# aiotsixsense.net
KiCad netlist of a schematic drawn in EAGLE
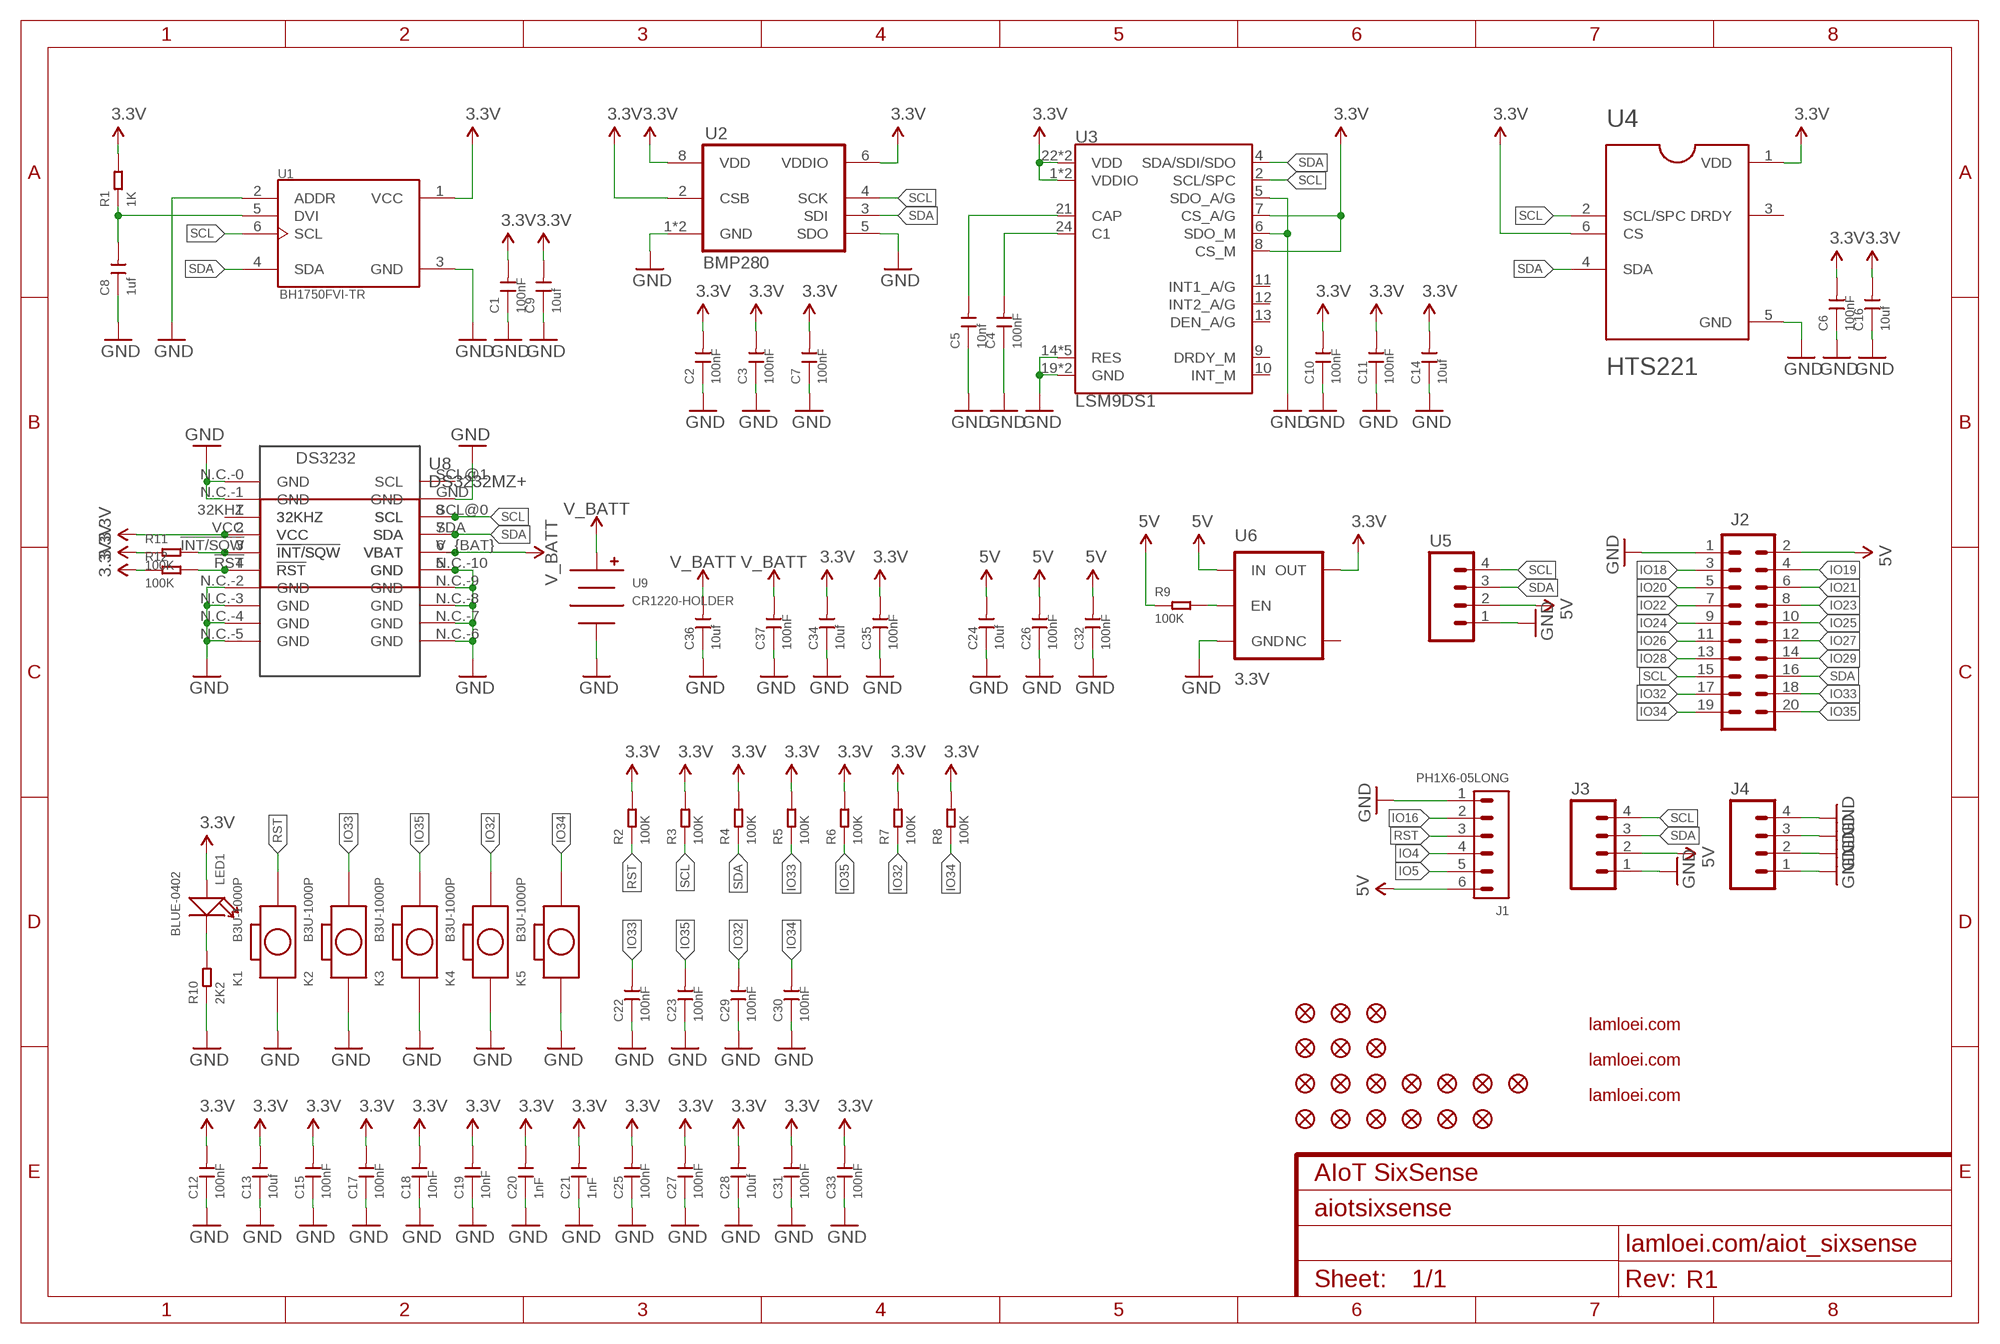
[diagram p0: schematic, sheet 1]

(export (version "E")
  (design (tool "Eeschema 10.0.6"))
  (components
    (comp (ref "C1")
      (value "100nF")
      (footprint "eagle-import:C0402")
      (fields (field (name "MPN") "CC0402JRNPO9BN470"))
      (libsource (lib "eagle-import") (part "CERAMIC-47PF-50V-5%-NP0(0402)"))
    )
    (comp (ref "C2")
      (value "100nF")
      (footprint "eagle-import:C0402")
      (fields (field (name "MPN") "CC0402JRNPO9BN470"))
      (libsource (lib "eagle-import") (part "CERAMIC-47PF-50V-5%-NP0(0402)"))
    )
    (comp (ref "C3")
      (value "100nF")
      (footprint "eagle-import:C0402")
      (fields (field (name "MPN") "CC0402JRNPO9BN470"))
      (libsource (lib "eagle-import") (part "CERAMIC-47PF-50V-5%-NP0(0402)"))
    )
    (comp (ref "C4")
      (value "100nF")
      (footprint "eagle-import:C0402")
      (fields (field (name "MPN") "CC0402JRNPO9BN470"))
      (libsource (lib "eagle-import") (part "CERAMIC-47PF-50V-5%-NP0(0402)"))
    )
    (comp (ref "C5")
      (value "10nf")
      (footprint "eagle-import:C0402")
      (fields (field (name "MPN") "CC0402KRX7R9BB103"))
      (libsource (lib "eagle-import") (part "CERAMIC-10NF-50V-10%-X7R(0402)"))
    )
    (comp (ref "C6")
      (value "100nF")
      (footprint "eagle-import:C0402")
      (fields (field (name "MPN") "CC0402JRNPO9BN470"))
      (libsource (lib "eagle-import") (part "CERAMIC-47PF-50V-5%-NP0(0402)"))
    )
    (comp (ref "C7")
      (value "100nF")
      (footprint "eagle-import:C0402")
      (fields (field (name "MPN") "CC0402JRNPO9BN470"))
      (libsource (lib "eagle-import") (part "CERAMIC-47PF-50V-5%-NP0(0402)"))
    )
    (comp (ref "C8")
      (value "1uf")
      (footprint "eagle-import:C0402")
      (fields (field (name "MPN") "CC0402KRX5R6BB105"))
      (libsource (lib "eagle-import") (part "CERAMIC-1UF-10V-10%-X5R(0402)"))
    )
    (comp (ref "C9")
      (value "10uf")
      (footprint "eagle-import:C0805")
      (fields (field (name "MPN") "CC0805MKX5R5BB226"))
      (libsource (lib "eagle-import") (part "CERAMIC-22UF-6.3V-20%-X5R(0805)"))
    )
    (comp (ref "C10")
      (value "100nF")
      (footprint "eagle-import:C0402")
      (fields (field (name "MPN") "CC0402JRNPO9BN470"))
      (libsource (lib "eagle-import") (part "CERAMIC-47PF-50V-5%-NP0(0402)"))
    )
    (comp (ref "C11")
      (value "100nF")
      (footprint "eagle-import:C0402")
      (fields (field (name "MPN") "CC0402JRNPO9BN470"))
      (libsource (lib "eagle-import") (part "CERAMIC-47PF-50V-5%-NP0(0402)"))
    )
    (comp (ref "C12")
      (value "100nF")
      (footprint "eagle-import:C0402")
      (fields (field (name "MPN") "CC0402JRNPO9BN470"))
      (libsource (lib "eagle-import") (part "CERAMIC-47PF-50V-5%-NP0(0402)"))
    )
    (comp (ref "C13")
      (value "10uf")
      (footprint "eagle-import:C0805")
      (fields (field (name "MPN") "CC0805MKX5R5BB226"))
      (libsource (lib "eagle-import") (part "CERAMIC-22UF-6.3V-20%-X5R(0805)"))
    )
    (comp (ref "C14")
      (value "10uf")
      (footprint "eagle-import:C0805")
      (fields (field (name "MPN") "CC0805MKX5R5BB226"))
      (libsource (lib "eagle-import") (part "CERAMIC-22UF-6.3V-20%-X5R(0805)"))
    )
    (comp (ref "C15")
      (value "100nF")
      (footprint "eagle-import:C0402")
      (fields (field (name "MPN") "CC0402JRNPO9BN470"))
      (libsource (lib "eagle-import") (part "CERAMIC-47PF-50V-5%-NP0(0402)"))
    )
    (comp (ref "C16")
      (value "10uf")
      (footprint "eagle-import:C0805")
      (fields (field (name "MPN") "CC0805MKX5R5BB226"))
      (libsource (lib "eagle-import") (part "CERAMIC-22UF-6.3V-20%-X5R(0805)"))
    )
    (comp (ref "C17")
      (value "100nF")
      (footprint "eagle-import:C0402")
      (fields (field (name "MPN") "CC0402JRNPO9BN470"))
      (libsource (lib "eagle-import") (part "CERAMIC-47PF-50V-5%-NP0(0402)"))
    )
    (comp (ref "C18")
      (value "10nF")
      (footprint "eagle-import:C0402")
      (fields (field (name "MPN") "CC0402JRNPO9BN470"))
      (libsource (lib "eagle-import") (part "CERAMIC-47PF-50V-5%-NP0(0402)"))
    )
    (comp (ref "C19")
      (value "10nF")
      (footprint "eagle-import:C0402")
      (fields (field (name "MPN") "CC0402JRNPO9BN470"))
      (libsource (lib "eagle-import") (part "CERAMIC-47PF-50V-5%-NP0(0402)"))
    )
    (comp (ref "C20")
      (value "1nF")
      (footprint "eagle-import:C0402")
      (fields (field (name "MPN") "CC0402JRNPO9BN470"))
      (libsource (lib "eagle-import") (part "CERAMIC-47PF-50V-5%-NP0(0402)"))
    )
    (comp (ref "C21")
      (value "1nF")
      (footprint "eagle-import:C0402")
      (fields (field (name "MPN") "CC0402JRNPO9BN470"))
      (libsource (lib "eagle-import") (part "CERAMIC-47PF-50V-5%-NP0(0402)"))
    )
    (comp (ref "C22")
      (value "100nF")
      (footprint "eagle-import:C0402")
      (fields (field (name "MPN") "CC0402JRNPO9BN470"))
      (libsource (lib "eagle-import") (part "CERAMIC-47PF-50V-5%-NP0(0402)"))
    )
    (comp (ref "C23")
      (value "100nF")
      (footprint "eagle-import:C0402")
      (fields (field (name "MPN") "CC0402JRNPO9BN470"))
      (libsource (lib "eagle-import") (part "CERAMIC-47PF-50V-5%-NP0(0402)"))
    )
    (comp (ref "C24")
      (value "10uf")
      (footprint "eagle-import:C0805")
      (fields (field (name "MPN") "CC0805MKX5R5BB226"))
      (libsource (lib "eagle-import") (part "CERAMIC-22UF-6.3V-20%-X5R(0805)"))
    )
    (comp (ref "C25")
      (value "100nF")
      (footprint "eagle-import:C0402")
      (fields (field (name "MPN") "CC0402JRNPO9BN470"))
      (libsource (lib "eagle-import") (part "CERAMIC-47PF-50V-5%-NP0(0402)"))
    )
    (comp (ref "C26")
      (value "100nF")
      (footprint "eagle-import:C0402")
      (fields (field (name "MPN") "CC0402JRNPO9BN470"))
      (libsource (lib "eagle-import") (part "CERAMIC-47PF-50V-5%-NP0(0402)"))
    )
    (comp (ref "C27")
      (value "100nF")
      (footprint "eagle-import:C0402")
      (fields (field (name "MPN") "CC0402JRNPO9BN470"))
      (libsource (lib "eagle-import") (part "CERAMIC-47PF-50V-5%-NP0(0402)"))
    )
    (comp (ref "C28")
      (value "10uf")
      (footprint "eagle-import:C0805")
      (fields (field (name "MPN") "CC0805MKX5R5BB226"))
      (libsource (lib "eagle-import") (part "CERAMIC-22UF-6.3V-20%-X5R(0805)"))
    )
    (comp (ref "C29")
      (value "100nF")
      (footprint "eagle-import:C0402")
      (fields (field (name "MPN") "CC0402JRNPO9BN470"))
      (libsource (lib "eagle-import") (part "CERAMIC-47PF-50V-5%-NP0(0402)"))
    )
    (comp (ref "C30")
      (value "100nF")
      (footprint "eagle-import:C0402")
      (fields (field (name "MPN") "CC0402JRNPO9BN470"))
      (libsource (lib "eagle-import") (part "CERAMIC-47PF-50V-5%-NP0(0402)"))
    )
    (comp (ref "C31")
      (value "100nF")
      (footprint "eagle-import:C0402")
      (fields (field (name "MPN") "CC0402JRNPO9BN470"))
      (libsource (lib "eagle-import") (part "CERAMIC-47PF-50V-5%-NP0(0402)"))
    )
    (comp (ref "C32")
      (value "100nF")
      (footprint "eagle-import:C0402")
      (fields (field (name "MPN") "CC0402JRNPO9BN470"))
      (libsource (lib "eagle-import") (part "CERAMIC-47PF-50V-5%-NP0(0402)"))
    )
    (comp (ref "C33")
      (value "100nF")
      (footprint "eagle-import:C0402")
      (fields (field (name "MPN") "CC0402JRNPO9BN470"))
      (libsource (lib "eagle-import") (part "CERAMIC-47PF-50V-5%-NP0(0402)"))
    )
    (comp (ref "C34")
      (value "10uf")
      (footprint "eagle-import:C0805")
      (fields (field (name "MPN") "CC0805MKX5R5BB226"))
      (libsource (lib "eagle-import") (part "CERAMIC-22UF-6.3V-20%-X5R(0805)"))
    )
    (comp (ref "C35")
      (value "100nF")
      (footprint "eagle-import:C0402")
      (fields (field (name "MPN") "CC0402JRNPO9BN470"))
      (libsource (lib "eagle-import") (part "CERAMIC-47PF-50V-5%-NP0(0402)"))
    )
    (comp (ref "C36")
      (value "10uf")
      (footprint "eagle-import:C0805")
      (fields (field (name "MPN") "CC0805MKX5R5BB226"))
      (libsource (lib "eagle-import") (part "CERAMIC-22UF-6.3V-20%-X5R(0805)"))
    )
    (comp (ref "C37")
      (value "100nF")
      (footprint "eagle-import:C0402")
      (fields (field (name "MPN") "CC0402JRNPO9BN470"))
      (libsource (lib "eagle-import") (part "CERAMIC-47PF-50V-5%-NP0(0402)"))
    )
    (comp (ref "J1")
      (value "PH1X6-05LONG")
      (footprint "eagle-import:PHL005-1-6")
      (libsource (lib "eagle-import") (part "PH1X6-05LONG"))
    )
    (comp (ref "J2")
      (value "M10X2")
      (footprint "eagle-import:2X10")
      (libsource (lib "eagle-import") (part "M10X2"))
    )
    (comp (ref "J3")
      (value "M04SMD_RA_FEMALE")
      (footprint "eagle-import:1X04_SMD_RA_FEMALE")
      (libsource (lib "eagle-import") (part "M04SMD_RA_FEMALE"))
    )
    (comp (ref "J4")
      (value "M04SMD_RA_FEMALE")
      (footprint "eagle-import:1X04_SMD_RA_FEMALE")
      (libsource (lib "eagle-import") (part "M04SMD_RA_FEMALE"))
    )
    (comp (ref "K1")
      (value "B3U-1000P")
      (footprint "eagle-import:SW2-SMD-3.0X2.5X1.2+0.4MM")
      (libsource (lib "eagle-import") (part "SMD-BUTTON-WITHOUT-BOSS-(2P-3X2.5MM)"))
    )
    (comp (ref "K2")
      (value "B3U-1000P")
      (footprint "eagle-import:SW2-SMD-3.0X2.5X1.2+0.4MM")
      (libsource (lib "eagle-import") (part "SMD-BUTTON-WITHOUT-BOSS-(2P-3X2.5MM)"))
    )
    (comp (ref "K3")
      (value "B3U-1000P")
      (footprint "eagle-import:SW2-SMD-3.0X2.5X1.2+0.4MM")
      (libsource (lib "eagle-import") (part "SMD-BUTTON-WITHOUT-BOSS-(2P-3X2.5MM)"))
    )
    (comp (ref "K4")
      (value "B3U-1000P")
      (footprint "eagle-import:SW2-SMD-3.0X2.5X1.2+0.4MM")
      (libsource (lib "eagle-import") (part "SMD-BUTTON-WITHOUT-BOSS-(2P-3X2.5MM)"))
    )
    (comp (ref "K5")
      (value "B3U-1000P")
      (footprint "eagle-import:SW2-SMD-3.0X2.5X1.2+0.4MM")
      (libsource (lib "eagle-import") (part "SMD-BUTTON-WITHOUT-BOSS-(2P-3X2.5MM)"))
    )
    (comp (ref "LED1")
      (value "BLUE-0402")
      (footprint "eagle-import:LED-0402")
      (fields (field (name "MPN") "BL-HB337A-AV-TRB"))
      (libsource (lib "eagle-import") (part "SMD-LED-CLEAR-BLUE(0402)"))
    )
    (comp (ref "R1")
      (value "1K")
      (footprint "eagle-import:R0402")
      (fields (field (name "MPN") "RC0402JR-071KL"))
      (libsource (lib "eagle-import") (part "SMD-RES-1K-5%-1/16W(0402)"))
    )
    (comp (ref "R2")
      (value "100K")
      (footprint "eagle-import:R0402")
      (fields (field (name "MPN") "RC0402FR-0722RL"))
      (libsource (lib "eagle-import") (part "SMD-RES-22R-1%-1/16W(0402)"))
    )
    (comp (ref "R3")
      (value "100K")
      (footprint "eagle-import:R0402")
      (fields (field (name "MPN") "RC0402FR-07100KL"))
      (libsource (lib "eagle-import") (part "SMD-RES-100K-1%-1/16W(0402)"))
    )
    (comp (ref "R4")
      (value "100K")
      (footprint "eagle-import:R0402")
      (fields (field (name "MPN") "RC0402FR-07100KL"))
      (libsource (lib "eagle-import") (part "SMD-RES-100K-1%-1/16W(0402)"))
    )
    (comp (ref "R5")
      (value "100K")
      (footprint "eagle-import:R0402")
      (fields (field (name "MPN") "RC0402FR-07100KL"))
      (libsource (lib "eagle-import") (part "SMD-RES-100K-1%-1/16W(0402)"))
    )
    (comp (ref "R6")
      (value "100K")
      (footprint "eagle-import:R0402")
      (fields (field (name "MPN") "RC0402FR-07100KL"))
      (libsource (lib "eagle-import") (part "SMD-RES-100K-1%-1/16W(0402)"))
    )
    (comp (ref "R7")
      (value "100K")
      (footprint "eagle-import:R0402")
      (fields (field (name "MPN") "RC0402FR-07100KL"))
      (libsource (lib "eagle-import") (part "SMD-RES-100K-1%-1/16W(0402)"))
    )
    (comp (ref "R8")
      (value "100K")
      (footprint "eagle-import:R0402")
      (fields (field (name "MPN") "RC0402FR-07100KL"))
      (libsource (lib "eagle-import") (part "SMD-RES-100K-1%-1/16W(0402)"))
    )
    (comp (ref "R9")
      (value "100K")
      (footprint "eagle-import:R0402")
      (fields (field (name "MPN") "RC0402FR-07100KL"))
      (libsource (lib "eagle-import") (part "SMD-RES-100K-1%-1/16W(0402)"))
    )
    (comp (ref "R10")
      (value "2K2")
      (footprint "eagle-import:R0402")
      (fields (field (name "MPN") "RC0402FR-0722RL"))
      (libsource (lib "eagle-import") (part "SMD-RES-22R-1%-1/16W(0402)"))
    )
    (comp (ref "R11")
      (value "100K")
      (footprint "eagle-import:R0402")
      (fields (field (name "MPN") "RC0402FR-07100KL"))
      (libsource (lib "eagle-import") (part "SMD-RES-100K-1%-1/16W(0402)"))
    )
    (comp (ref "R12")
      (value "100K")
      (footprint "eagle-import:R0402")
      (fields (field (name "MPN") "RC0402FR-07100KL"))
      (libsource (lib "eagle-import") (part "SMD-RES-100K-1%-1/16W(0402)"))
    )
    (comp (ref "U1")
      (value "BH1750FVI-TR")
      (footprint "eagle-import:SOTFL50P300X75-6N")
      (fields (field (name "MF") "Rohm"))
      (libsource (lib "eagle-import") (part "BH1750FVI-TR"))
    )
    (comp (ref "U2")
      (value "BMP280")
      (footprint "eagle-import:BMP280")
      (libsource (lib "eagle-import") (part "BMP280"))
    )
    (comp (ref "U3")
      (value "LSM9DS1")
      (footprint "eagle-import:LGA-24-3.5X3")
      (libsource (lib "eagle-import") (part "LSM9DS1"))
    )
    (comp (ref "U4")
      (value "HTS221")
      (footprint "eagle-import:LGA6R75P3X2_200X200X90")
      (libsource (lib "eagle-import") (part "HTS221"))
    )
    (comp (ref "U5")
      (value "M04LONGPADS")
      (footprint "eagle-import:1X04_LONGPADS")
      (libsource (lib "eagle-import") (part "M04LONGPADS"))
    )
    (comp (ref "U6")
      (value "3.3V")
      (footprint "eagle-import:SOT23-5")
      (libsource (lib "eagle-import") (part "V_REG_AP2112K-3.3V"))
    )
    (comp (ref "U7")
      (value "DS3232")
      (footprint "eagle-import:SO20-2")
      (libsource (lib "eagle-import") (part "DS3232"))
    )
    (comp (ref "U8")
      (value "DS3232MZ+")
      (footprint "eagle-import:SOIC127P600X175-8N")
      (fields (field (name "RS_PART_NUMBER") "9237642"))
      (libsource (lib "eagle-import") (part "DS3232MZ+"))
    )
    (comp (ref "U9")
      (value "CR1220-HOLDER")
      (footprint "eagle-import:HARWIN-CR1220")
      (libsource (lib "eagle-import") (part "CR1220-HOLDER"))
    )
    (comp (ref "ZFCB1")
      (value "FIDUCIAL1X2")
      (footprint "eagle-import:FIDUCIAL-1X2")
      (libsource (lib "eagle-import") (part "FIDUCIAL1X2"))
    )
    (comp (ref "ZFCB2")
      (value "FIDUCIAL1X2")
      (footprint "eagle-import:FIDUCIAL-1X2")
      (libsource (lib "eagle-import") (part "FIDUCIAL1X2"))
    )
    (comp (ref "ZFCB3")
      (value "FIDUCIAL1X2")
      (footprint "eagle-import:FIDUCIAL-1X2")
      (libsource (lib "eagle-import") (part "FIDUCIAL1X2"))
    )
    (comp (ref "ZFCT1")
      (value "FIDUCIAL1X2")
      (footprint "eagle-import:FIDUCIAL-1X2")
      (libsource (lib "eagle-import") (part "FIDUCIAL1X2"))
    )
    (comp (ref "ZFCT2")
      (value "FIDUCIAL1X2")
      (footprint "eagle-import:FIDUCIAL-1X2")
      (libsource (lib "eagle-import") (part "FIDUCIAL1X2"))
    )
    (comp (ref "ZFCT3")
      (value "FIDUCIAL1X2")
      (footprint "eagle-import:FIDUCIAL-1X2")
      (libsource (lib "eagle-import") (part "FIDUCIAL1X2"))
    )
    (comp (ref "ZFDB1")
      (value "FIDUCIAL1X2")
      (footprint "eagle-import:FIDUCIAL-1X2")
      (libsource (lib "eagle-import") (part "FIDUCIAL1X2"))
    )
    (comp (ref "ZFDB2")
      (value "FIDUCIAL1X2")
      (footprint "eagle-import:FIDUCIAL-1X2")
      (libsource (lib "eagle-import") (part "FIDUCIAL1X2"))
    )
    (comp (ref "ZFDB3")
      (value "FIDUCIAL1X2")
      (footprint "eagle-import:FIDUCIAL-1X2")
      (libsource (lib "eagle-import") (part "FIDUCIAL1X2"))
    )
    (comp (ref "ZFDB4")
      (value "FIDUCIAL1X2")
      (footprint "eagle-import:FIDUCIAL-1X2")
      (libsource (lib "eagle-import") (part "FIDUCIAL1X2"))
    )
    (comp (ref "ZFDB5")
      (value "FIDUCIAL1X2")
      (footprint "eagle-import:FIDUCIAL-1X2")
      (libsource (lib "eagle-import") (part "FIDUCIAL1X2"))
    )
    (comp (ref "ZFDB6")
      (value "FIDUCIAL1X2")
      (footprint "eagle-import:FIDUCIAL-1X2")
      (libsource (lib "eagle-import") (part "FIDUCIAL1X2"))
    )
    (comp (ref "ZFDT1")
      (value "FIDUCIAL1X2")
      (footprint "eagle-import:FIDUCIAL-1X2")
      (libsource (lib "eagle-import") (part "FIDUCIAL1X2"))
    )
    (comp (ref "ZFDT2")
      (value "FIDUCIAL1X2")
      (footprint "eagle-import:FIDUCIAL-1X2")
      (libsource (lib "eagle-import") (part "FIDUCIAL1X2"))
    )
    (comp (ref "ZFDT3")
      (value "FIDUCIAL1X2")
      (footprint "eagle-import:FIDUCIAL-1X2")
      (libsource (lib "eagle-import") (part "FIDUCIAL1X2"))
    )
    (comp (ref "ZFDT4")
      (value "FIDUCIAL1X2")
      (footprint "eagle-import:FIDUCIAL-1X2")
      (libsource (lib "eagle-import") (part "FIDUCIAL1X2"))
    )
    (comp (ref "ZFDT5")
      (value "FIDUCIAL1X2")
      (footprint "eagle-import:FIDUCIAL-1X2")
      (libsource (lib "eagle-import") (part "FIDUCIAL1X2"))
    )
    (comp (ref "ZFDT6")
      (value "FIDUCIAL1X2")
      (footprint "eagle-import:FIDUCIAL-1X2")
      (libsource (lib "eagle-import") (part "FIDUCIAL1X2"))
    )
    (comp (ref "ZFDT7")
      (value "FIDUCIAL1X2")
      (footprint "eagle-import:FIDUCIAL-1X2")
      (libsource (lib "eagle-import") (part "FIDUCIAL1X2"))
    )
    (comp (ref "ZL1")
      (value "LAMLOEI_BIGLOGO")
      (footprint "eagle-import:LAMLOEI_BIGLOGO")
      (libsource (lib "eagle-import") (part "LAMLOEI_BIGLOGO"))
    )
    (comp (ref "ZL2")
      (value "LAMLEOI_LOGO_3")
      (footprint "eagle-import:LAMLEOI_LOGO_3")
      (libsource (lib "eagle-import") (part "LAMLEOI_LOGO_3"))
    )
    (comp (ref "ZL3")
      (value "LAMLEOI_LOGO_3")
      (footprint "eagle-import:LAMLEOI_LOGO_3")
      (libsource (lib "eagle-import") (part "LAMLEOI_LOGO_3"))
    )
  )
  (nets
    (net (code "1") (name "3.3V") (class "Default")
      (node (ref "C1") (pin "2") (pinfunction "2_2") (pintype "passive"))
      (node (ref "C10") (pin "2") (pinfunction "2_2") (pintype "passive"))
      (node (ref "C11") (pin "2") (pinfunction "2_2") (pintype "passive"))
      (node (ref "C12") (pin "2") (pinfunction "2_2") (pintype "passive"))
      (node (ref "C13") (pin "2") (pinfunction "2_2") (pintype "passive"))
      (node (ref "C14") (pin "2") (pinfunction "2_2") (pintype "passive"))
      (node (ref "C15") (pin "2") (pinfunction "2_2") (pintype "passive"))
      (node (ref "C16") (pin "2") (pinfunction "2_2") (pintype "passive"))
      (node (ref "C17") (pin "2") (pinfunction "2_2") (pintype "passive"))
      (node (ref "C18") (pin "2") (pinfunction "2_2") (pintype "passive"))
      (node (ref "C19") (pin "2") (pinfunction "2_2") (pintype "passive"))
      (node (ref "C2") (pin "2") (pinfunction "2_2") (pintype "passive"))
      (node (ref "C20") (pin "2") (pinfunction "2_2") (pintype "passive"))
      (node (ref "C21") (pin "2") (pinfunction "2_2") (pintype "passive"))
      (node (ref "C25") (pin "2") (pinfunction "2_2") (pintype "passive"))
      (node (ref "C27") (pin "2") (pinfunction "2_2") (pintype "passive"))
      (node (ref "C28") (pin "2") (pinfunction "2_2") (pintype "passive"))
      (node (ref "C3") (pin "2") (pinfunction "2_2") (pintype "passive"))
      (node (ref "C31") (pin "2") (pinfunction "2_2") (pintype "passive"))
      (node (ref "C33") (pin "2") (pinfunction "2_2") (pintype "passive"))
      (node (ref "C34") (pin "2") (pinfunction "2_2") (pintype "passive"))
      (node (ref "C35") (pin "2") (pinfunction "2_2") (pintype "passive"))
      (node (ref "C6") (pin "2") (pinfunction "2_2") (pintype "passive"))
      (node (ref "C7") (pin "2") (pinfunction "2_2") (pintype "passive"))
      (node (ref "C9") (pin "2") (pinfunction "2_2") (pintype "passive"))
      (node (ref "LED1") (pin "+") (pinfunction "+_+") (pintype "passive"))
      (node (ref "R1") (pin "2") (pinfunction "2_2") (pintype "passive"))
      (node (ref "R11") (pin "1") (pinfunction "1_1") (pintype "passive"))
      (node (ref "R12") (pin "1") (pinfunction "1_1") (pintype "passive"))
      (node (ref "R2") (pin "2") (pinfunction "2_2") (pintype "passive"))
      (node (ref "R3") (pin "2") (pinfunction "2_2") (pintype "passive"))
      (node (ref "R4") (pin "2") (pinfunction "2_2") (pintype "passive"))
      (node (ref "R5") (pin "2") (pinfunction "2_2") (pintype "passive"))
      (node (ref "R6") (pin "2") (pinfunction "2_2") (pintype "passive"))
      (node (ref "R7") (pin "2") (pinfunction "2_2") (pintype "passive"))
      (node (ref "R8") (pin "2") (pinfunction "2_2") (pintype "passive"))
      (node (ref "U1") (pin "1") (pinfunction "VCC_1") (pintype "power_in"))
      (node (ref "U2") (pin "2") (pinfunction "CSB_2") (pintype "input"))
      (node (ref "U2") (pin "6") (pinfunction "VDDIO_6") (pintype "power_in"))
      (node (ref "U2") (pin "8") (pinfunction "VDD_8") (pintype "power_in"))
      (node (ref "U3") (pin "1") (pinfunction "VDDIO_1") (pintype "bidirectional"))
      (node (ref "U3") (pin "22") (pinfunction "VDD_22") (pintype "bidirectional"))
      (node (ref "U3") (pin "23") (pinfunction "VDD_23") (pintype "bidirectional"))
      (node (ref "U3") (pin "3") (pinfunction "VDDIO_3") (pintype "bidirectional"))
      (node (ref "U3") (pin "7") (pinfunction "CS_A/G_7") (pintype "bidirectional"))
      (node (ref "U3") (pin "8") (pinfunction "CS_M_8") (pintype "bidirectional"))
      (node (ref "U4") (pin "1") (pinfunction "VDD_1") (pintype "power_in"))
      (node (ref "U4") (pin "6") (pinfunction "CS_6") (pintype "input"))
      (node (ref "U6") (pin "5") (pinfunction "OUT_5") (pintype "passive"))
      (node (ref "U7") (pin "VCC") (pinfunction "VCC_VCC") (pintype "bidirectional"))
      (node (ref "U8") (pin "2") (pinfunction "VCC_2") (pintype "bidirectional"))
    )
    (net (code "2") (name "5V") (class "Default")
      (node (ref "C24") (pin "2") (pinfunction "2_2") (pintype "passive"))
      (node (ref "C26") (pin "2") (pinfunction "2_2") (pintype "passive"))
      (node (ref "C32") (pin "2") (pinfunction "2_2") (pintype "passive"))
      (node (ref "J1") (pin "6") (pinfunction "6_6") (pintype "bidirectional"))
      (node (ref "J2") (pin "2") (pinfunction "2_2") (pintype "passive"))
      (node (ref "J3") (pin "2") (pinfunction "2_2") (pintype "passive"))
      (node (ref "R9") (pin "1") (pinfunction "1_1") (pintype "passive"))
      (node (ref "U5") (pin "2") (pinfunction "2_2") (pintype "passive"))
      (node (ref "U6") (pin "1") (pinfunction "IN_1") (pintype "input"))
    )
    (net (code "3") (name "GND") (class "Default")
      (node (ref "C1") (pin "1") (pinfunction "1_1") (pintype "passive"))
      (node (ref "C10") (pin "1") (pinfunction "1_1") (pintype "passive"))
      (node (ref "C11") (pin "1") (pinfunction "1_1") (pintype "passive"))
      (node (ref "C12") (pin "1") (pinfunction "1_1") (pintype "passive"))
      (node (ref "C13") (pin "1") (pinfunction "1_1") (pintype "passive"))
      (node (ref "C14") (pin "1") (pinfunction "1_1") (pintype "passive"))
      (node (ref "C15") (pin "1") (pinfunction "1_1") (pintype "passive"))
      (node (ref "C16") (pin "1") (pinfunction "1_1") (pintype "passive"))
      (node (ref "C17") (pin "1") (pinfunction "1_1") (pintype "passive"))
      (node (ref "C18") (pin "1") (pinfunction "1_1") (pintype "passive"))
      (node (ref "C19") (pin "1") (pinfunction "1_1") (pintype "passive"))
      (node (ref "C2") (pin "1") (pinfunction "1_1") (pintype "passive"))
      (node (ref "C20") (pin "1") (pinfunction "1_1") (pintype "passive"))
      (node (ref "C21") (pin "1") (pinfunction "1_1") (pintype "passive"))
      (node (ref "C22") (pin "1") (pinfunction "1_1") (pintype "passive"))
      (node (ref "C23") (pin "1") (pinfunction "1_1") (pintype "passive"))
      (node (ref "C24") (pin "1") (pinfunction "1_1") (pintype "passive"))
      (node (ref "C25") (pin "1") (pinfunction "1_1") (pintype "passive"))
      (node (ref "C26") (pin "1") (pinfunction "1_1") (pintype "passive"))
      (node (ref "C27") (pin "1") (pinfunction "1_1") (pintype "passive"))
      (node (ref "C28") (pin "1") (pinfunction "1_1") (pintype "passive"))
      (node (ref "C29") (pin "1") (pinfunction "1_1") (pintype "passive"))
      (node (ref "C3") (pin "1") (pinfunction "1_1") (pintype "passive"))
      (node (ref "C30") (pin "1") (pinfunction "1_1") (pintype "passive"))
      (node (ref "C31") (pin "1") (pinfunction "1_1") (pintype "passive"))
      (node (ref "C32") (pin "1") (pinfunction "1_1") (pintype "passive"))
      (node (ref "C33") (pin "1") (pinfunction "1_1") (pintype "passive"))
      (node (ref "C34") (pin "1") (pinfunction "1_1") (pintype "passive"))
      (node (ref "C35") (pin "1") (pinfunction "1_1") (pintype "passive"))
      (node (ref "C36") (pin "1") (pinfunction "1_1") (pintype "passive"))
      (node (ref "C37") (pin "1") (pinfunction "1_1") (pintype "passive"))
      (node (ref "C4") (pin "1") (pinfunction "1_1") (pintype "passive"))
      (node (ref "C5") (pin "1") (pinfunction "1_1") (pintype "passive"))
      (node (ref "C6") (pin "1") (pinfunction "1_1") (pintype "passive"))
      (node (ref "C7") (pin "1") (pinfunction "1_1") (pintype "passive"))
      (node (ref "C8") (pin "1") (pinfunction "1_1") (pintype "passive"))
      (node (ref "C9") (pin "1") (pinfunction "1_1") (pintype "passive"))
      (node (ref "J1") (pin "1") (pinfunction "1_1") (pintype "bidirectional"))
      (node (ref "J2") (pin "1") (pinfunction "1_1") (pintype "passive"))
      (node (ref "J3") (pin "1") (pinfunction "1_1") (pintype "passive"))
      (node (ref "J4") (pin "1") (pinfunction "1_1") (pintype "passive"))
      (node (ref "J4") (pin "2") (pinfunction "2_2") (pintype "passive"))
      (node (ref "J4") (pin "3") (pinfunction "3_3") (pintype "passive"))
      (node (ref "J4") (pin "4") (pinfunction "4_4") (pintype "passive"))
      (node (ref "K1") (pin "1") (pinfunction "1_1") (pintype "bidirectional"))
      (node (ref "K2") (pin "1") (pinfunction "1_1") (pintype "bidirectional"))
      (node (ref "K3") (pin "1") (pinfunction "1_1") (pintype "bidirectional"))
      (node (ref "K4") (pin "1") (pinfunction "1_1") (pintype "bidirectional"))
      (node (ref "K5") (pin "1") (pinfunction "1_1") (pintype "bidirectional"))
      (node (ref "R10") (pin "1") (pinfunction "1_1") (pintype "passive"))
      (node (ref "U1") (pin "2") (pinfunction "ADDR_2") (pintype "input"))
      (node (ref "U1") (pin "3") (pinfunction "GND_3") (pintype "power_in"))
      (node (ref "U2") (pin "1") (pinfunction "GND_1") (pintype "power_in"))
      (node (ref "U2") (pin "5") (pinfunction "SDO_5") (pintype "input"))
      (node (ref "U2") (pin "7") (pinfunction "GND_7") (pintype "power_in"))
      (node (ref "U3") (pin "14") (pinfunction "RES_14") (pintype "bidirectional"))
      (node (ref "U3") (pin "15") (pinfunction "RES_15") (pintype "bidirectional"))
      (node (ref "U3") (pin "16") (pinfunction "RES_16") (pintype "bidirectional"))
      (node (ref "U3") (pin "17") (pinfunction "RES_17") (pintype "bidirectional"))
      (node (ref "U3") (pin "18") (pinfunction "RES_18") (pintype "bidirectional"))
      (node (ref "U3") (pin "19") (pinfunction "GND_19") (pintype "bidirectional"))
      (node (ref "U3") (pin "20") (pinfunction "GND_20") (pintype "bidirectional"))
      (node (ref "U3") (pin "5") (pinfunction "SDO_A/G_5") (pintype "bidirectional"))
      (node (ref "U3") (pin "6") (pinfunction "SDO_M_6") (pintype "bidirectional"))
      (node (ref "U4") (pin "5") (pinfunction "GND_5") (pintype "passive"))
      (node (ref "U5") (pin "1") (pinfunction "1_1") (pintype "passive"))
      (node (ref "U6") (pin "2") (pinfunction "GND_2") (pintype "input"))
      (node (ref "U7") (pin "GND") (pinfunction "GND_GND") (pintype "bidirectional"))
      (node (ref "U7") (pin "N.C.-0") (pinfunction "GND_N.C.-0") (pintype "bidirectional"))
      (node (ref "U7") (pin "N.C.-1") (pinfunction "GND_N.C.-1") (pintype "bidirectional"))
      (node (ref "U7") (pin "N.C.-10") (pinfunction "GND_N.C.-10") (pintype "bidirectional"))
      (node (ref "U7") (pin "N.C.-2") (pinfunction "GND_N.C.-2") (pintype "bidirectional"))
      (node (ref "U7") (pin "N.C.-3") (pinfunction "GND_N.C.-3") (pintype "bidirectional"))
      (node (ref "U7") (pin "N.C.-4") (pinfunction "GND_N.C.-4") (pintype "bidirectional"))
      (node (ref "U7") (pin "N.C.-5") (pinfunction "GND_N.C.-5") (pintype "bidirectional"))
      (node (ref "U7") (pin "N.C.-6") (pinfunction "GND_N.C.-6") (pintype "bidirectional"))
      (node (ref "U7") (pin "N.C.-7") (pinfunction "GND_N.C.-7") (pintype "bidirectional"))
      (node (ref "U7") (pin "N.C.-8") (pinfunction "GND_N.C.-8") (pintype "bidirectional"))
      (node (ref "U7") (pin "N.C.-9") (pinfunction "GND_N.C.-9") (pintype "bidirectional"))
      (node (ref "U8") (pin "5") (pinfunction "GND_5") (pintype "bidirectional"))
      (node (ref "U9") (pin "NEG") (pinfunction "NEG_NEG") (pintype "bidirectional"))
    )
    (net (code "4") (name "IO4") (class "Default")
      (node (ref "J1") (pin "4") (pinfunction "4_4") (pintype "bidirectional"))
    )
    (net (code "5") (name "IO5") (class "Default")
      (node (ref "J1") (pin "5") (pinfunction "5_5") (pintype "bidirectional"))
    )
    (net (code "6") (name "IO16") (class "Default")
      (node (ref "J1") (pin "2") (pinfunction "2_2") (pintype "bidirectional"))
    )
    (net (code "7") (name "IO18") (class "Default")
      (node (ref "J2") (pin "3") (pinfunction "3_3") (pintype "passive"))
    )
    (net (code "8") (name "IO19") (class "Default")
      (node (ref "J2") (pin "4") (pinfunction "4_4") (pintype "passive"))
    )
    (net (code "9") (name "IO20") (class "Default")
      (node (ref "J2") (pin "5") (pinfunction "5_5") (pintype "passive"))
    )
    (net (code "10") (name "IO21") (class "Default")
      (node (ref "J2") (pin "6") (pinfunction "6_6") (pintype "passive"))
    )
    (net (code "11") (name "IO22") (class "Default")
      (node (ref "J2") (pin "7") (pinfunction "7_7") (pintype "passive"))
    )
    (net (code "12") (name "IO23") (class "Default")
      (node (ref "J2") (pin "8") (pinfunction "8_8") (pintype "passive"))
    )
    (net (code "13") (name "IO24") (class "Default")
      (node (ref "J2") (pin "9") (pinfunction "9_9") (pintype "passive"))
    )
    (net (code "14") (name "IO25") (class "Default")
      (node (ref "J2") (pin "10") (pinfunction "10_10") (pintype "passive"))
    )
    (net (code "15") (name "IO26") (class "Default")
      (node (ref "J2") (pin "11") (pinfunction "11_11") (pintype "passive"))
    )
    (net (code "16") (name "IO27") (class "Default")
      (node (ref "J2") (pin "12") (pinfunction "12_12") (pintype "passive"))
    )
    (net (code "17") (name "IO28") (class "Default")
      (node (ref "J2") (pin "13") (pinfunction "13_13") (pintype "passive"))
    )
    (net (code "18") (name "IO29") (class "Default")
      (node (ref "J2") (pin "14") (pinfunction "14_14") (pintype "passive"))
    )
    (net (code "19") (name "IO32") (class "Default")
      (node (ref "C29") (pin "2") (pinfunction "2_2") (pintype "passive"))
      (node (ref "J2") (pin "17") (pinfunction "17_17") (pintype "passive"))
      (node (ref "K4") (pin "2") (pinfunction "2_2") (pintype "bidirectional"))
      (node (ref "R7") (pin "1") (pinfunction "1_1") (pintype "passive"))
    )
    (net (code "20") (name "IO33") (class "Default")
      (node (ref "C22") (pin "2") (pinfunction "2_2") (pintype "passive"))
      (node (ref "J2") (pin "18") (pinfunction "18_18") (pintype "passive"))
      (node (ref "K2") (pin "2") (pinfunction "2_2") (pintype "bidirectional"))
      (node (ref "R5") (pin "1") (pinfunction "1_1") (pintype "passive"))
    )
    (net (code "21") (name "IO34") (class "Default")
      (node (ref "C30") (pin "2") (pinfunction "2_2") (pintype "passive"))
      (node (ref "J2") (pin "19") (pinfunction "19_19") (pintype "passive"))
      (node (ref "K5") (pin "2") (pinfunction "2_2") (pintype "bidirectional"))
      (node (ref "R8") (pin "1") (pinfunction "1_1") (pintype "passive"))
    )
    (net (code "22") (name "IO35") (class "Default")
      (node (ref "C23") (pin "2") (pinfunction "2_2") (pintype "passive"))
      (node (ref "J2") (pin "20") (pinfunction "20_20") (pintype "passive"))
      (node (ref "K3") (pin "2") (pinfunction "2_2") (pintype "bidirectional"))
      (node (ref "R6") (pin "1") (pinfunction "1_1") (pintype "passive"))
    )
    (net (code "23") (name "Net-(LED1-Pad-)") (class "Default")
      (node (ref "LED1") (pin "-") (pinfunction "-_-") (pintype "passive"))
      (node (ref "R10") (pin "2") (pinfunction "2_2") (pintype "passive"))
    )
    (net (code "24") (name "Net-(U1-DVI)") (class "Default")
      (node (ref "C8") (pin "2") (pinfunction "2_2") (pintype "passive"))
      (node (ref "R1") (pin "1") (pinfunction "1_1") (pintype "passive"))
      (node (ref "U1") (pin "5") (pinfunction "DVI_5") (pintype "input"))
    )
    (net (code "25") (name "Net-(U3-C1)") (class "Default")
      (node (ref "C4") (pin "2") (pinfunction "2_2") (pintype "passive"))
      (node (ref "U3") (pin "24") (pinfunction "C1_24") (pintype "bidirectional"))
    )
    (net (code "26") (name "Net-(U3-CAP)") (class "Default")
      (node (ref "C5") (pin "2") (pinfunction "2_2") (pintype "passive"))
      (node (ref "U3") (pin "21") (pinfunction "CAP_21") (pintype "bidirectional"))
    )
    (net (code "27") (name "Net-(U6-EN)") (class "Default")
      (node (ref "R9") (pin "2") (pinfunction "2_2") (pintype "passive"))
      (node (ref "U6") (pin "3") (pinfunction "EN_3") (pintype "input"))
    )
    (net (code "28") (name "Net-(U7-RST)") (class "Default")
      (node (ref "R12") (pin "2") (pinfunction "2_2") (pintype "passive"))
      (node (ref "U7") (pin "!RST") (pinfunction "RST_!RST") (pintype "bidirectional"))
      (node (ref "U8") (pin "4") (pinfunction "~{RST}_4") (pintype "bidirectional"))
    )
    (net (code "29") (name "Net-(U7-~{INT{slash}SQW})") (class "Default")
      (node (ref "R11") (pin "2") (pinfunction "2_2") (pintype "passive"))
      (node (ref "U7") (pin "!INT/SQW") (pinfunction "~{INT/SQW}_!INT/SQW") (pintype "bidirectional"))
      (node (ref "U8") (pin "3") (pinfunction "~{INT}/SQW_3") (pintype "bidirectional"))
    )
    (net (code "30") (name "Net-(U8-32KHZ)") (class "Default")
      (node (ref "U7") (pin "32KHZ") (pinfunction "32KHZ_32KHZ") (pintype "bidirectional"))
      (node (ref "U8") (pin "1") (pinfunction "32KHZ_1") (pintype "bidirectional"))
    )
    (net (code "31") (name "RST") (class "Default")
      (node (ref "J1") (pin "3") (pinfunction "3_3") (pintype "bidirectional"))
      (node (ref "K1") (pin "2") (pinfunction "2_2") (pintype "bidirectional"))
      (node (ref "R2") (pin "1") (pinfunction "1_1") (pintype "passive"))
    )
    (net (code "32") (name "SCL") (class "Default")
      (node (ref "J2") (pin "15") (pinfunction "15_15") (pintype "passive"))
      (node (ref "J3") (pin "4") (pinfunction "4_4") (pintype "passive"))
      (node (ref "R3") (pin "1") (pinfunction "1_1") (pintype "passive"))
      (node (ref "U1") (pin "6") (pinfunction "SCL_6") (pintype "input"))
      (node (ref "U2") (pin "4") (pinfunction "SCK_4") (pintype "bidirectional"))
      (node (ref "U3") (pin "2") (pinfunction "SCL/SPC_2") (pintype "bidirectional"))
      (node (ref "U4") (pin "2") (pinfunction "SCL/SPC_2") (pintype "input"))
      (node (ref "U5") (pin "4") (pinfunction "4_4") (pintype "passive"))
      (node (ref "U7") (pin "SCL@0") (pinfunction "SCL_SCL@0") (pintype "bidirectional"))
      (node (ref "U8") (pin "8") (pinfunction "SCL_8") (pintype "bidirectional"))
    )
    (net (code "33") (name "SDA") (class "Default")
      (node (ref "J2") (pin "16") (pinfunction "16_16") (pintype "passive"))
      (node (ref "J3") (pin "3") (pinfunction "3_3") (pintype "passive"))
      (node (ref "R4") (pin "1") (pinfunction "1_1") (pintype "passive"))
      (node (ref "U1") (pin "4") (pinfunction "SDA_4") (pintype "bidirectional"))
      (node (ref "U2") (pin "3") (pinfunction "SDI_3") (pintype "bidirectional"))
      (node (ref "U3") (pin "4") (pinfunction "SDA/SDI/SDO_4") (pintype "bidirectional"))
      (node (ref "U4") (pin "4") (pinfunction "SDA_4") (pintype "bidirectional"))
      (node (ref "U5") (pin "3") (pinfunction "3_3") (pintype "passive"))
      (node (ref "U7") (pin "SDA") (pinfunction "SDA_SDA") (pintype "bidirectional"))
      (node (ref "U8") (pin "7") (pinfunction "SDA_7") (pintype "bidirectional"))
    )
    (net (code "34") (name "V_BATT") (class "Default")
      (node (ref "C36") (pin "2") (pinfunction "2_2") (pintype "passive"))
      (node (ref "C37") (pin "2") (pinfunction "2_2") (pintype "passive"))
      (node (ref "U7") (pin "V_{BAT}") (pinfunction "VBAT_V_{BAT}") (pintype "bidirectional"))
      (node (ref "U8") (pin "6") (pinfunction "VBAT_6") (pintype "bidirectional"))
      (node (ref "U9") (pin "POS") (pinfunction "POS_POS") (pintype "bidirectional"))
    )
    (net (code "35") (name "unconnected-(U3-DEN_A{slash}G-Pad13)") (class "Default")
      (node (ref "U3") (pin "13") (pinfunction "DEN_A/G_13") (pintype "bidirectional"))
    )
    (net (code "36") (name "unconnected-(U3-DRDY_M-Pad9)") (class "Default")
      (node (ref "U3") (pin "9") (pinfunction "DRDY_M_9") (pintype "bidirectional"))
    )
    (net (code "37") (name "unconnected-(U3-INT1_A{slash}G-Pad11)") (class "Default")
      (node (ref "U3") (pin "11") (pinfunction "INT1_A/G_11") (pintype "bidirectional"))
    )
    (net (code "38") (name "unconnected-(U3-INT2_A{slash}G-Pad12)") (class "Default")
      (node (ref "U3") (pin "12") (pinfunction "INT2_A/G_12") (pintype "bidirectional"))
    )
    (net (code "39") (name "unconnected-(U3-INT_M-Pad10)") (class "Default")
      (node (ref "U3") (pin "10") (pinfunction "INT_M_10") (pintype "bidirectional"))
    )
    (net (code "40") (name "unconnected-(U4-DRDY-Pad3)") (class "Default")
      (node (ref "U4") (pin "3") (pinfunction "DRDY_3") (pintype "output"))
    )
    (net (code "41") (name "unconnected-(U6-NC-Pad4)") (class "Default")
      (node (ref "U6") (pin "4") (pinfunction "NC_4") (pintype "input"))
    )
    (net (code "42") (name "unconnected-(U7-SCL-PadSCL@1)") (class "Default")
      (node (ref "U7") (pin "SCL@1") (pinfunction "SCL_SCL@1") (pintype "bidirectional"))
    )
  )
)
